# light_up_board.net
KiCad netlist of a schematic drawn in EAGLE
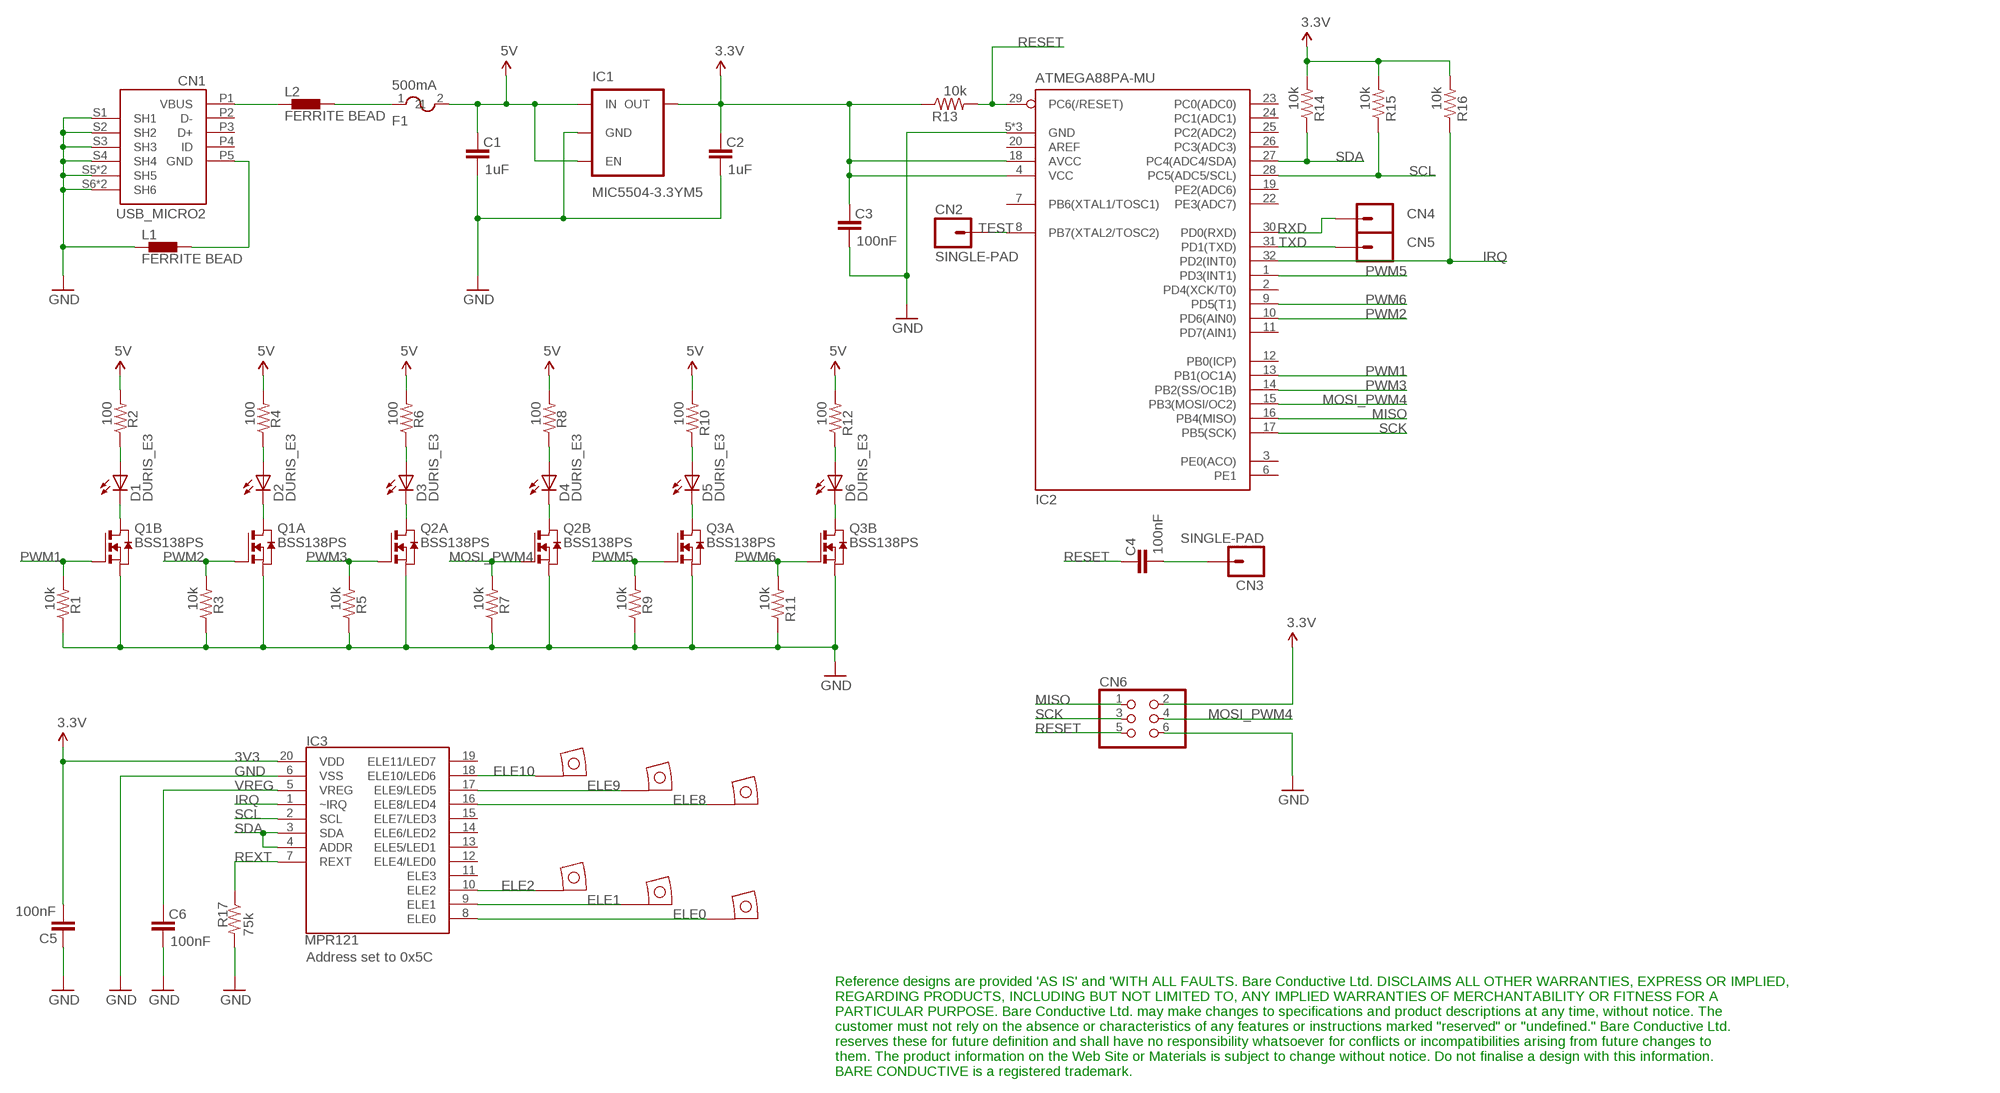
[diagram p0: schematic, sheet 1]

(export (version "E")
  (design (tool "Eeschema 10.0.6"))
  (components
    (comp (ref "C1")
      (value "1uF")
      (footprint "eagle-import:0402-CAP")
      (libsource (lib "eagle-import") (part "CAP0402-CAP"))
    )
    (comp (ref "C2")
      (value "1uF")
      (footprint "eagle-import:0402-CAP")
      (libsource (lib "eagle-import") (part "CAP0402-CAP"))
    )
    (comp (ref "C3")
      (value "100nF")
      (footprint "eagle-import:0402-CAP")
      (libsource (lib "eagle-import") (part "CAP0402-CAP"))
    )
    (comp (ref "C4")
      (value "100nF")
      (footprint "eagle-import:0402-CAP")
      (libsource (lib "eagle-import") (part "CAP0402-CAP"))
    )
    (comp (ref "C5")
      (value "100nF")
      (footprint "eagle-import:0402-CAP")
      (libsource (lib "eagle-import") (part "CAP0402-CAP"))
    )
    (comp (ref "C6")
      (value "100nF")
      (footprint "eagle-import:0402-CAP")
      (libsource (lib "eagle-import") (part "CAP0402-CAP"))
    )
    (comp (ref "CN1")
      (value "USB_MICRO2")
      (footprint "eagle-import:USB_MICRO_B_SCK_2_TANGS")
      (libsource (lib "eagle-import") (part "USB_MICRO2"))
    )
    (comp (ref "CN2")
      (value "SINGLE-PAD")
      (footprint "eagle-import:1MM_0.4MM_DRILL_PAD")
      (libsource (lib "eagle-import") (part "SINGLE-PAD"))
    )
    (comp (ref "CN3")
      (value "SINGLE-PAD")
      (footprint "eagle-import:1MM_0.4MM_DRILL_PAD")
      (libsource (lib "eagle-import") (part "SINGLE-PAD"))
    )
    (comp (ref "CN4")
      (value "SINGLE-PAD")
      (footprint "eagle-import:1MM_0.4MM_DRILL_PAD")
      (libsource (lib "eagle-import") (part "SINGLE-PAD"))
    )
    (comp (ref "CN5")
      (value "SINGLE-PAD")
      (footprint "eagle-import:1MM_0.4MM_DRILL_PAD")
      (libsource (lib "eagle-import") (part "SINGLE-PAD"))
    )
    (comp (ref "CN6")
      (value "ICSP")
      (footprint "eagle-import:2X03_1.27_SQ1_0.4_DRILL")
      (libsource (lib "eagle-import") (part "PINHD-2X3SQ1_1.27_0.4_DRILL"))
    )
    (comp (ref "D1")
      (value "DURIS_E3")
      (footprint "eagle-import:PLCC2_3X1.4")
      (libsource (lib "eagle-import") (part "DURIS_E3"))
    )
    (comp (ref "D2")
      (value "DURIS_E3")
      (footprint "eagle-import:PLCC2_3X1.4")
      (libsource (lib "eagle-import") (part "DURIS_E3"))
    )
    (comp (ref "D3")
      (value "DURIS_E3")
      (footprint "eagle-import:PLCC2_3X1.4")
      (libsource (lib "eagle-import") (part "DURIS_E3"))
    )
    (comp (ref "D4")
      (value "DURIS_E3")
      (footprint "eagle-import:PLCC2_3X1.4")
      (libsource (lib "eagle-import") (part "DURIS_E3"))
    )
    (comp (ref "D5")
      (value "DURIS_E3")
      (footprint "eagle-import:PLCC2_3X1.4")
      (libsource (lib "eagle-import") (part "DURIS_E3"))
    )
    (comp (ref "D6")
      (value "DURIS_E3")
      (footprint "eagle-import:PLCC2_3X1.4")
      (libsource (lib "eagle-import") (part "DURIS_E3"))
    )
    (comp (ref "F1")
      (value "500mA")
      (footprint "eagle-import:MF-PSMF050X-2")
      (libsource (lib "eagle-import") (part "PTC"))
    )
    (comp (ref "IC1")
      (value "MIC5504-3.3YM5")
      (footprint "eagle-import:SOT23-5")
      (libsource (lib "eagle-import") (part "V_REG_LDOSMD"))
    )
    (comp (ref "IC2")
      (value "ATMEGA88PA-MU")
      (footprint "eagle-import:HVQFN32-MEDPADS")
      (libsource (lib "eagle-import") (part "MEGAX8PBMU/MEDPADS"))
    )
    (comp (ref "IC3")
      (value "MPR121")
      (footprint "eagle-import:QFN-20-0.4MM-LONGPADS-NORESIST")
      (libsource (lib "eagle-import") (part "MPR121QR2/LONGPADS-NORESIST"))
    )
    (comp (ref "L1")
      (value "FERRITE BEAD")
      (footprint "eagle-import:0402")
      (libsource (lib "eagle-import") (part "BLM15HB121SN1"))
    )
    (comp (ref "L2")
      (value "FERRITE BEAD")
      (footprint "eagle-import:0402")
      (libsource (lib "eagle-import") (part "BLM15HB121SN1"))
    )
    (comp (ref "Q1")
      (value "BSS138PS")
      (footprint "eagle-import:SOT363_PHILIPS")
      (libsource (lib "eagle-import") (part "BSS138PS"))
    )
    (comp (ref "Q2")
      (value "BSS138PS")
      (footprint "eagle-import:SOT363_PHILIPS")
      (libsource (lib "eagle-import") (part "BSS138PS"))
    )
    (comp (ref "Q3")
      (value "BSS138PS")
      (footprint "eagle-import:SOT363_PHILIPS")
      (libsource (lib "eagle-import") (part "BSS138PS"))
    )
    (comp (ref "R1")
      (value "10k")
      (footprint "eagle-import:0402-RES")
      (libsource (lib "eagle-import") (part "RESISTOR0402-RES"))
    )
    (comp (ref "R2")
      (value "100")
      (footprint "eagle-import:0402-RES")
      (libsource (lib "eagle-import") (part "RESISTOR0402-RES"))
    )
    (comp (ref "R3")
      (value "10k")
      (footprint "eagle-import:0402-RES")
      (libsource (lib "eagle-import") (part "RESISTOR0402-RES"))
    )
    (comp (ref "R4")
      (value "100")
      (footprint "eagle-import:0402-RES")
      (libsource (lib "eagle-import") (part "RESISTOR0402-RES"))
    )
    (comp (ref "R5")
      (value "10k")
      (footprint "eagle-import:0402-RES")
      (libsource (lib "eagle-import") (part "RESISTOR0402-RES"))
    )
    (comp (ref "R6")
      (value "100")
      (footprint "eagle-import:0402-RES")
      (libsource (lib "eagle-import") (part "RESISTOR0402-RES"))
    )
    (comp (ref "R7")
      (value "10k")
      (footprint "eagle-import:0402-RES")
      (libsource (lib "eagle-import") (part "RESISTOR0402-RES"))
    )
    (comp (ref "R8")
      (value "100")
      (footprint "eagle-import:0402-RES")
      (libsource (lib "eagle-import") (part "RESISTOR0402-RES"))
    )
    (comp (ref "R9")
      (value "10k")
      (footprint "eagle-import:0402-RES")
      (libsource (lib "eagle-import") (part "RESISTOR0402-RES"))
    )
    (comp (ref "R10")
      (value "100")
      (footprint "eagle-import:0402-RES")
      (libsource (lib "eagle-import") (part "RESISTOR0402-RES"))
    )
    (comp (ref "R11")
      (value "10k")
      (footprint "eagle-import:0402-RES")
      (libsource (lib "eagle-import") (part "RESISTOR0402-RES"))
    )
    (comp (ref "R12")
      (value "100")
      (footprint "eagle-import:0402-RES")
      (libsource (lib "eagle-import") (part "RESISTOR0402-RES"))
    )
    (comp (ref "R13")
      (value "10k")
      (footprint "eagle-import:0402-RES")
      (libsource (lib "eagle-import") (part "RESISTOR0402-RES"))
    )
    (comp (ref "R14")
      (value "10k")
      (footprint "eagle-import:0402-RES")
      (libsource (lib "eagle-import") (part "RESISTOR0402-RES"))
    )
    (comp (ref "R15")
      (value "10k")
      (footprint "eagle-import:0402-RES")
      (libsource (lib "eagle-import") (part "RESISTOR0402-RES"))
    )
    (comp (ref "R16")
      (value "10k")
      (footprint "eagle-import:0402-RES")
      (libsource (lib "eagle-import") (part "RESISTOR0402-RES"))
    )
    (comp (ref "R17")
      (value "75k")
      (footprint "eagle-import:0402-RES")
      (libsource (lib "eagle-import") (part "RESISTOR0402-RES"))
    )
    (comp (ref "U$1")
      (value "EPSK-ELEC_2.0")
      (footprint "eagle-import:EPSK_ELEC_2.0")
      (libsource (lib "eagle-import") (part "EPSK-ELEC_2.0"))
    )
    (comp (ref "U$2")
      (value "EPSK-ELEC_2.0")
      (footprint "eagle-import:EPSK_ELEC_2.0")
      (libsource (lib "eagle-import") (part "EPSK-ELEC_2.0"))
    )
    (comp (ref "U$3")
      (value "EPSK-ELEC_2.0")
      (footprint "eagle-import:EPSK_ELEC_2.0")
      (libsource (lib "eagle-import") (part "EPSK-ELEC_2.0"))
    )
    (comp (ref "U$4")
      (value "EPSK-ELEC_2.0")
      (footprint "eagle-import:EPSK_ELEC_2.0")
      (libsource (lib "eagle-import") (part "EPSK-ELEC_2.0"))
    )
    (comp (ref "U$5")
      (value "EPSK-ELEC_2.0")
      (footprint "eagle-import:EPSK_ELEC_2.0")
      (libsource (lib "eagle-import") (part "EPSK-ELEC_2.0"))
    )
    (comp (ref "U$6")
      (value "EPSK-ELEC_2.0")
      (footprint "eagle-import:EPSK_ELEC_2.0")
      (libsource (lib "eagle-import") (part "EPSK-ELEC_2.0"))
    )
  )
  (nets
    (net (code "1") (name "/ELE0") (class "Default")
      (node (ref "IC3") (pin "8") (pinfunction "ELE0_8") (pintype "bidirectional"))
      (node (ref "U$6") (pin "1") (pinfunction "1_1") (pintype "bidirectional"))
    )
    (net (code "2") (name "/ELE1") (class "Default")
      (node (ref "IC3") (pin "9") (pinfunction "ELE1_9") (pintype "bidirectional"))
      (node (ref "U$4") (pin "1") (pinfunction "1_1") (pintype "bidirectional"))
    )
    (net (code "3") (name "/ELE2") (class "Default")
      (node (ref "IC3") (pin "10") (pinfunction "ELE2_10") (pintype "bidirectional"))
      (node (ref "U$2") (pin "1") (pinfunction "1_1") (pintype "bidirectional"))
    )
    (net (code "4") (name "/ELE8") (class "Default")
      (node (ref "IC3") (pin "16") (pinfunction "ELE8/LED4_16") (pintype "bidirectional"))
      (node (ref "U$5") (pin "1") (pinfunction "1_1") (pintype "bidirectional"))
    )
    (net (code "5") (name "/ELE9") (class "Default")
      (node (ref "IC3") (pin "17") (pinfunction "ELE9/LED5_17") (pintype "bidirectional"))
      (node (ref "U$3") (pin "1") (pinfunction "1_1") (pintype "bidirectional"))
    )
    (net (code "6") (name "/ELE10") (class "Default")
      (node (ref "IC3") (pin "18") (pinfunction "ELE10/LED6_18") (pintype "bidirectional"))
      (node (ref "U$1") (pin "1") (pinfunction "1_1") (pintype "bidirectional"))
    )
    (net (code "7") (name "/IRQ") (class "Default")
      (node (ref "IC2") (pin "32") (pinfunction "PD2(INT0)_32") (pintype "bidirectional"))
      (node (ref "IC3") (pin "1") (pinfunction "~{IRQ}_1") (pintype "bidirectional"))
      (node (ref "R16") (pin "1") (pinfunction "1_1") (pintype "passive"))
    )
    (net (code "8") (name "/MISO") (class "Default")
      (node (ref "CN6") (pin "1") (pinfunction "1_1") (pintype "passive"))
      (node (ref "IC2") (pin "16") (pinfunction "PB4(MISO)_16") (pintype "bidirectional"))
    )
    (net (code "9") (name "/MOSI_PWM4") (class "Default")
      (node (ref "CN6") (pin "4") (pinfunction "4_4") (pintype "passive"))
      (node (ref "IC2") (pin "15") (pinfunction "PB3(MOSI/OC2)_15") (pintype "bidirectional"))
      (node (ref "Q2") (pin "5") (pinfunction "G_5") (pintype "passive"))
      (node (ref "R7") (pin "2") (pinfunction "2_2") (pintype "passive"))
    )
    (net (code "10") (name "/PWM1") (class "Default")
      (node (ref "IC2") (pin "13") (pinfunction "PB1(OC1A)_13") (pintype "bidirectional"))
      (node (ref "Q1") (pin "5") (pinfunction "G_5") (pintype "passive"))
      (node (ref "R1") (pin "2") (pinfunction "2_2") (pintype "passive"))
    )
    (net (code "11") (name "/PWM2") (class "Default")
      (node (ref "IC2") (pin "10") (pinfunction "PD6(AIN0)_10") (pintype "bidirectional"))
      (node (ref "Q1") (pin "2") (pinfunction "G_2") (pintype "passive"))
      (node (ref "R3") (pin "2") (pinfunction "2_2") (pintype "passive"))
    )
    (net (code "12") (name "/PWM3") (class "Default")
      (node (ref "IC2") (pin "14") (pinfunction "PB2(SS/OC1B)_14") (pintype "bidirectional"))
      (node (ref "Q2") (pin "2") (pinfunction "G_2") (pintype "passive"))
      (node (ref "R5") (pin "2") (pinfunction "2_2") (pintype "passive"))
    )
    (net (code "13") (name "/PWM5") (class "Default")
      (node (ref "IC2") (pin "1") (pinfunction "PD3(INT1)_1") (pintype "bidirectional"))
      (node (ref "Q3") (pin "2") (pinfunction "G_2") (pintype "passive"))
      (node (ref "R9") (pin "2") (pinfunction "2_2") (pintype "passive"))
    )
    (net (code "14") (name "/PWM6") (class "Default")
      (node (ref "IC2") (pin "9") (pinfunction "PD5(T1)_9") (pintype "bidirectional"))
      (node (ref "Q3") (pin "5") (pinfunction "G_5") (pintype "passive"))
      (node (ref "R11") (pin "2") (pinfunction "2_2") (pintype "passive"))
    )
    (net (code "15") (name "/RESET") (class "Default")
      (node (ref "C4") (pin "2") (pinfunction "2_2") (pintype "passive"))
      (node (ref "CN6") (pin "5") (pinfunction "5_5") (pintype "passive"))
      (node (ref "IC2") (pin "29") (pinfunction "PC6(/RESET)_29") (pintype "bidirectional"))
      (node (ref "R13") (pin "2") (pinfunction "2_2") (pintype "passive"))
    )
    (net (code "16") (name "/REXT") (class "Default")
      (node (ref "IC3") (pin "7") (pinfunction "REXT_7") (pintype "bidirectional"))
      (node (ref "R17") (pin "1") (pinfunction "1_1") (pintype "passive"))
    )
    (net (code "17") (name "/RXD") (class "Default")
      (node (ref "CN4") (pin "1") (pinfunction "1_1") (pintype "passive"))
      (node (ref "IC2") (pin "30") (pinfunction "PD0(RXD)_30") (pintype "bidirectional"))
    )
    (net (code "18") (name "/SCK") (class "Default")
      (node (ref "CN6") (pin "3") (pinfunction "3_3") (pintype "passive"))
      (node (ref "IC2") (pin "17") (pinfunction "PB5(SCK)_17") (pintype "bidirectional"))
    )
    (net (code "19") (name "/SCL") (class "Default")
      (node (ref "IC2") (pin "28") (pinfunction "PC5(ADC5/SCL)_28") (pintype "bidirectional"))
      (node (ref "IC3") (pin "2") (pinfunction "SCL_2") (pintype "bidirectional"))
      (node (ref "R15") (pin "1") (pinfunction "1_1") (pintype "passive"))
    )
    (net (code "20") (name "/SDA") (class "Default")
      (node (ref "IC2") (pin "27") (pinfunction "PC4(ADC4/SDA)_27") (pintype "bidirectional"))
      (node (ref "IC3") (pin "3") (pinfunction "SDA_3") (pintype "bidirectional"))
      (node (ref "IC3") (pin "4") (pinfunction "ADDR_4") (pintype "bidirectional"))
      (node (ref "R14") (pin "1") (pinfunction "1_1") (pintype "passive"))
    )
    (net (code "21") (name "/TEST") (class "Default")
      (node (ref "CN2") (pin "1") (pinfunction "1_1") (pintype "passive"))
      (node (ref "IC2") (pin "8") (pinfunction "PB7(XTAL2/TOSC2)_8") (pintype "bidirectional"))
    )
    (net (code "22") (name "/TXD") (class "Default")
      (node (ref "CN5") (pin "1") (pinfunction "1_1") (pintype "passive"))
      (node (ref "IC2") (pin "31") (pinfunction "PD1(TXD)_31") (pintype "bidirectional"))
    )
    (net (code "23") (name "/VREG") (class "Default")
      (node (ref "C6") (pin "2") (pinfunction "2_2") (pintype "passive"))
      (node (ref "IC3") (pin "5") (pinfunction "VREG_5") (pintype "bidirectional"))
    )
    (net (code "24") (name "3.3V") (class "Default")
      (node (ref "C2") (pin "2") (pinfunction "2_2") (pintype "passive"))
      (node (ref "C3") (pin "2") (pinfunction "2_2") (pintype "passive"))
      (node (ref "C5") (pin "1") (pinfunction "1_1") (pintype "passive"))
      (node (ref "CN6") (pin "2") (pinfunction "2_2") (pintype "passive"))
      (node (ref "IC1") (pin "5") (pinfunction "OUT_5") (pintype "passive"))
      (node (ref "IC2") (pin "18") (pinfunction "AVCC_18") (pintype "power_in"))
      (node (ref "IC2") (pin "4") (pinfunction "VCC_4") (pintype "power_in"))
      (node (ref "IC3") (pin "20") (pinfunction "VDD_20") (pintype "bidirectional"))
      (node (ref "R13") (pin "1") (pinfunction "1_1") (pintype "passive"))
      (node (ref "R14") (pin "2") (pinfunction "2_2") (pintype "passive"))
      (node (ref "R15") (pin "2") (pinfunction "2_2") (pintype "passive"))
      (node (ref "R16") (pin "2") (pinfunction "2_2") (pintype "passive"))
    )
    (net (code "25") (name "5V") (class "Default")
      (node (ref "C1") (pin "2") (pinfunction "2_2") (pintype "passive"))
      (node (ref "F1") (pin "2") (pinfunction "2_2") (pintype "bidirectional"))
      (node (ref "IC1") (pin "1") (pinfunction "IN_1") (pintype "input"))
      (node (ref "IC1") (pin "3") (pinfunction "EN_3") (pintype "input"))
      (node (ref "R10") (pin "2") (pinfunction "2_2") (pintype "passive"))
      (node (ref "R12") (pin "2") (pinfunction "2_2") (pintype "passive"))
      (node (ref "R2") (pin "2") (pinfunction "2_2") (pintype "passive"))
      (node (ref "R4") (pin "2") (pinfunction "2_2") (pintype "passive"))
      (node (ref "R6") (pin "2") (pinfunction "2_2") (pintype "passive"))
      (node (ref "R8") (pin "2") (pinfunction "2_2") (pintype "passive"))
    )
    (net (code "26") (name "GND") (class "Default")
      (node (ref "C1") (pin "1") (pinfunction "1_1") (pintype "passive"))
      (node (ref "C2") (pin "1") (pinfunction "1_1") (pintype "passive"))
      (node (ref "C3") (pin "1") (pinfunction "1_1") (pintype "passive"))
      (node (ref "C5") (pin "2") (pinfunction "2_2") (pintype "passive"))
      (node (ref "C6") (pin "1") (pinfunction "1_1") (pintype "passive"))
      (node (ref "CN1") (pin "S1") (pinfunction "SH1_S1") (pintype "passive"))
      (node (ref "CN1") (pin "S2") (pinfunction "SH2_S2") (pintype "passive"))
      (node (ref "CN1") (pin "S3") (pinfunction "SH3_S3") (pintype "passive"))
      (node (ref "CN1") (pin "S4") (pinfunction "SH4_S4") (pintype "passive"))
      (node (ref "CN1") (pin "S5") (pinfunction "SH5_S5") (pintype "passive"))
      (node (ref "CN1") (pin "S6") (pinfunction "SH6_S6") (pintype "passive"))
      (node (ref "CN1") (pin "S7") (pinfunction "SH5_S7") (pintype "passive"))
      (node (ref "CN1") (pin "S8") (pinfunction "SH6_S8") (pintype "passive"))
      (node (ref "CN6") (pin "6") (pinfunction "6_6") (pintype "passive"))
      (node (ref "IC1") (pin "2") (pinfunction "GND_2") (pintype "input"))
      (node (ref "IC2") (pin "21") (pinfunction "GND_21") (pintype "power_in"))
      (node (ref "IC2") (pin "5") (pinfunction "GND_5") (pintype "power_in"))
      (node (ref "IC2") (pin "EXP") (pinfunction "GND_EXP") (pintype "power_in"))
      (node (ref "IC3") (pin "6") (pinfunction "VSS_6") (pintype "bidirectional"))
      (node (ref "L1") (pin "1") (pinfunction "1_1") (pintype "passive"))
      (node (ref "Q1") (pin "1") (pinfunction "S_1") (pintype "passive"))
      (node (ref "Q1") (pin "4") (pinfunction "S_4") (pintype "passive"))
      (node (ref "Q2") (pin "1") (pinfunction "S_1") (pintype "passive"))
      (node (ref "Q2") (pin "4") (pinfunction "S_4") (pintype "passive"))
      (node (ref "Q3") (pin "1") (pinfunction "S_1") (pintype "passive"))
      (node (ref "Q3") (pin "4") (pinfunction "S_4") (pintype "passive"))
      (node (ref "R1") (pin "1") (pinfunction "1_1") (pintype "passive"))
      (node (ref "R11") (pin "1") (pinfunction "1_1") (pintype "passive"))
      (node (ref "R17") (pin "2") (pinfunction "2_2") (pintype "passive"))
      (node (ref "R3") (pin "1") (pinfunction "1_1") (pintype "passive"))
      (node (ref "R5") (pin "1") (pinfunction "1_1") (pintype "passive"))
      (node (ref "R7") (pin "1") (pinfunction "1_1") (pintype "passive"))
      (node (ref "R9") (pin "1") (pinfunction "1_1") (pintype "passive"))
    )
    (net (code "27") (name "Net-(C4-Pad1)") (class "Default")
      (node (ref "C4") (pin "1") (pinfunction "1_1") (pintype "passive"))
      (node (ref "CN3") (pin "1") (pinfunction "1_1") (pintype "passive"))
    )
    (net (code "28") (name "Net-(CN1-GND)") (class "Default")
      (node (ref "CN1") (pin "P5") (pinfunction "GND_P5") (pintype "passive"))
      (node (ref "L1") (pin "2") (pinfunction "2_2") (pintype "passive"))
    )
    (net (code "29") (name "Net-(CN1-VBUS)") (class "Default")
      (node (ref "CN1") (pin "P1") (pinfunction "VBUS_P1") (pintype "power_in"))
      (node (ref "L2") (pin "1") (pinfunction "1_1") (pintype "passive"))
    )
    (net (code "30") (name "Net-(D1-C)") (class "Default")
      (node (ref "D1") (pin "K") (pinfunction "C_K") (pintype "passive"))
      (node (ref "Q1") (pin "3") (pinfunction "D_3") (pintype "passive"))
    )
    (net (code "31") (name "Net-(D1-PadA)") (class "Default")
      (node (ref "D1") (pin "A") (pinfunction "A_A") (pintype "passive"))
      (node (ref "R2") (pin "1") (pinfunction "1_1") (pintype "passive"))
    )
    (net (code "32") (name "Net-(D2-C)") (class "Default")
      (node (ref "D2") (pin "K") (pinfunction "C_K") (pintype "passive"))
      (node (ref "Q1") (pin "6") (pinfunction "D_6") (pintype "passive"))
    )
    (net (code "33") (name "Net-(D2-PadA)") (class "Default")
      (node (ref "D2") (pin "A") (pinfunction "A_A") (pintype "passive"))
      (node (ref "R4") (pin "1") (pinfunction "1_1") (pintype "passive"))
    )
    (net (code "34") (name "Net-(D3-C)") (class "Default")
      (node (ref "D3") (pin "K") (pinfunction "C_K") (pintype "passive"))
      (node (ref "Q2") (pin "6") (pinfunction "D_6") (pintype "passive"))
    )
    (net (code "35") (name "Net-(D3-PadA)") (class "Default")
      (node (ref "D3") (pin "A") (pinfunction "A_A") (pintype "passive"))
      (node (ref "R6") (pin "1") (pinfunction "1_1") (pintype "passive"))
    )
    (net (code "36") (name "Net-(D4-C)") (class "Default")
      (node (ref "D4") (pin "K") (pinfunction "C_K") (pintype "passive"))
      (node (ref "Q2") (pin "3") (pinfunction "D_3") (pintype "passive"))
    )
    (net (code "37") (name "Net-(D4-PadA)") (class "Default")
      (node (ref "D4") (pin "A") (pinfunction "A_A") (pintype "passive"))
      (node (ref "R8") (pin "1") (pinfunction "1_1") (pintype "passive"))
    )
    (net (code "38") (name "Net-(D5-C)") (class "Default")
      (node (ref "D5") (pin "K") (pinfunction "C_K") (pintype "passive"))
      (node (ref "Q3") (pin "6") (pinfunction "D_6") (pintype "passive"))
    )
    (net (code "39") (name "Net-(D5-PadA)") (class "Default")
      (node (ref "D5") (pin "A") (pinfunction "A_A") (pintype "passive"))
      (node (ref "R10") (pin "1") (pinfunction "1_1") (pintype "passive"))
    )
    (net (code "40") (name "Net-(D6-C)") (class "Default")
      (node (ref "D6") (pin "K") (pinfunction "C_K") (pintype "passive"))
      (node (ref "Q3") (pin "3") (pinfunction "D_3") (pintype "passive"))
    )
    (net (code "41") (name "Net-(D6-PadA)") (class "Default")
      (node (ref "D6") (pin "A") (pinfunction "A_A") (pintype "passive"))
      (node (ref "R12") (pin "1") (pinfunction "1_1") (pintype "passive"))
    )
    (net (code "42") (name "Net-(F1-Pad1)") (class "Default")
      (node (ref "F1") (pin "1") (pinfunction "1_1") (pintype "bidirectional"))
      (node (ref "L2") (pin "2") (pinfunction "2_2") (pintype "passive"))
    )
    (net (code "43") (name "unconnected-(CN1-D+-PadP3)") (class "Default")
      (node (ref "CN1") (pin "P3") (pinfunction "D+_P3") (pintype "bidirectional"))
    )
    (net (code "44") (name "unconnected-(CN1-D--PadP2)") (class "Default")
      (node (ref "CN1") (pin "P2") (pinfunction "D-_P2") (pintype "bidirectional"))
    )
    (net (code "45") (name "unconnected-(CN1-ID-PadP4)") (class "Default")
      (node (ref "CN1") (pin "P4") (pinfunction "ID_P4") (pintype "bidirectional"))
    )
    (net (code "46") (name "unconnected-(IC2-AREF-Pad20)") (class "Default")
      (node (ref "IC2") (pin "20") (pinfunction "AREF_20") (pintype "passive"))
    )
    (net (code "47") (name "unconnected-(IC2-PB0(ICP)-Pad12)") (class "Default")
      (node (ref "IC2") (pin "12") (pinfunction "PB0(ICP)_12") (pintype "bidirectional"))
    )
    (net (code "48") (name "unconnected-(IC2-PB6(XTAL1{slash}TOSC1)-Pad7)") (class "Default")
      (node (ref "IC2") (pin "7") (pinfunction "PB6(XTAL1/TOSC1)_7") (pintype "bidirectional"))
    )
    (net (code "49") (name "unconnected-(IC2-PC0(ADC0)-Pad23)") (class "Default")
      (node (ref "IC2") (pin "23") (pinfunction "PC0(ADC0)_23") (pintype "bidirectional"))
    )
    (net (code "50") (name "unconnected-(IC2-PC1(ADC1)-Pad24)") (class "Default")
      (node (ref "IC2") (pin "24") (pinfunction "PC1(ADC1)_24") (pintype "bidirectional"))
    )
    (net (code "51") (name "unconnected-(IC2-PC2(ADC2)-Pad25)") (class "Default")
      (node (ref "IC2") (pin "25") (pinfunction "PC2(ADC2)_25") (pintype "bidirectional"))
    )
    (net (code "52") (name "unconnected-(IC2-PC3(ADC3)-Pad26)") (class "Default")
      (node (ref "IC2") (pin "26") (pinfunction "PC3(ADC3)_26") (pintype "bidirectional"))
    )
    (net (code "53") (name "unconnected-(IC2-PD4(XCK{slash}T0)-Pad2)") (class "Default")
      (node (ref "IC2") (pin "2") (pinfunction "PD4(XCK/T0)_2") (pintype "bidirectional"))
    )
    (net (code "54") (name "unconnected-(IC2-PD7(AIN1)-Pad11)") (class "Default")
      (node (ref "IC2") (pin "11") (pinfunction "PD7(AIN1)_11") (pintype "bidirectional"))
    )
    (net (code "55") (name "unconnected-(IC2-PE0(ACO)-Pad3)") (class "Default")
      (node (ref "IC2") (pin "3") (pinfunction "PE0(ACO)_3") (pintype "bidirectional"))
    )
    (net (code "56") (name "unconnected-(IC2-PE1-Pad6)") (class "Default")
      (node (ref "IC2") (pin "6") (pinfunction "PE1_6") (pintype "bidirectional"))
    )
    (net (code "57") (name "unconnected-(IC2-PE2(ADC6)-Pad19)") (class "Default")
      (node (ref "IC2") (pin "19") (pinfunction "PE2(ADC6)_19") (pintype "bidirectional"))
    )
    (net (code "58") (name "unconnected-(IC2-PE3(ADC7)-Pad22)") (class "Default")
      (node (ref "IC2") (pin "22") (pinfunction "PE3(ADC7)_22") (pintype "bidirectional"))
    )
    (net (code "59") (name "unconnected-(IC3-ELE3-Pad11)") (class "Default")
      (node (ref "IC3") (pin "11") (pinfunction "ELE3_11") (pintype "bidirectional"))
    )
    (net (code "60") (name "unconnected-(IC3-ELE4{slash}LED0-Pad12)") (class "Default")
      (node (ref "IC3") (pin "12") (pinfunction "ELE4/LED0_12") (pintype "bidirectional"))
    )
    (net (code "61") (name "unconnected-(IC3-ELE5{slash}LED1-Pad13)") (class "Default")
      (node (ref "IC3") (pin "13") (pinfunction "ELE5/LED1_13") (pintype "bidirectional"))
    )
    (net (code "62") (name "unconnected-(IC3-ELE6{slash}LED2-Pad14)") (class "Default")
      (node (ref "IC3") (pin "14") (pinfunction "ELE6/LED2_14") (pintype "bidirectional"))
    )
    (net (code "63") (name "unconnected-(IC3-ELE7{slash}LED3-Pad15)") (class "Default")
      (node (ref "IC3") (pin "15") (pinfunction "ELE7/LED3_15") (pintype "bidirectional"))
    )
    (net (code "64") (name "unconnected-(IC3-ELE11{slash}LED7-Pad19)") (class "Default")
      (node (ref "IC3") (pin "19") (pinfunction "ELE11/LED7_19") (pintype "bidirectional"))
    )
  )
)
